# Lora_GPS_Shield_v1_1.net
KiCad netlist of a schematic drawn in EAGLE
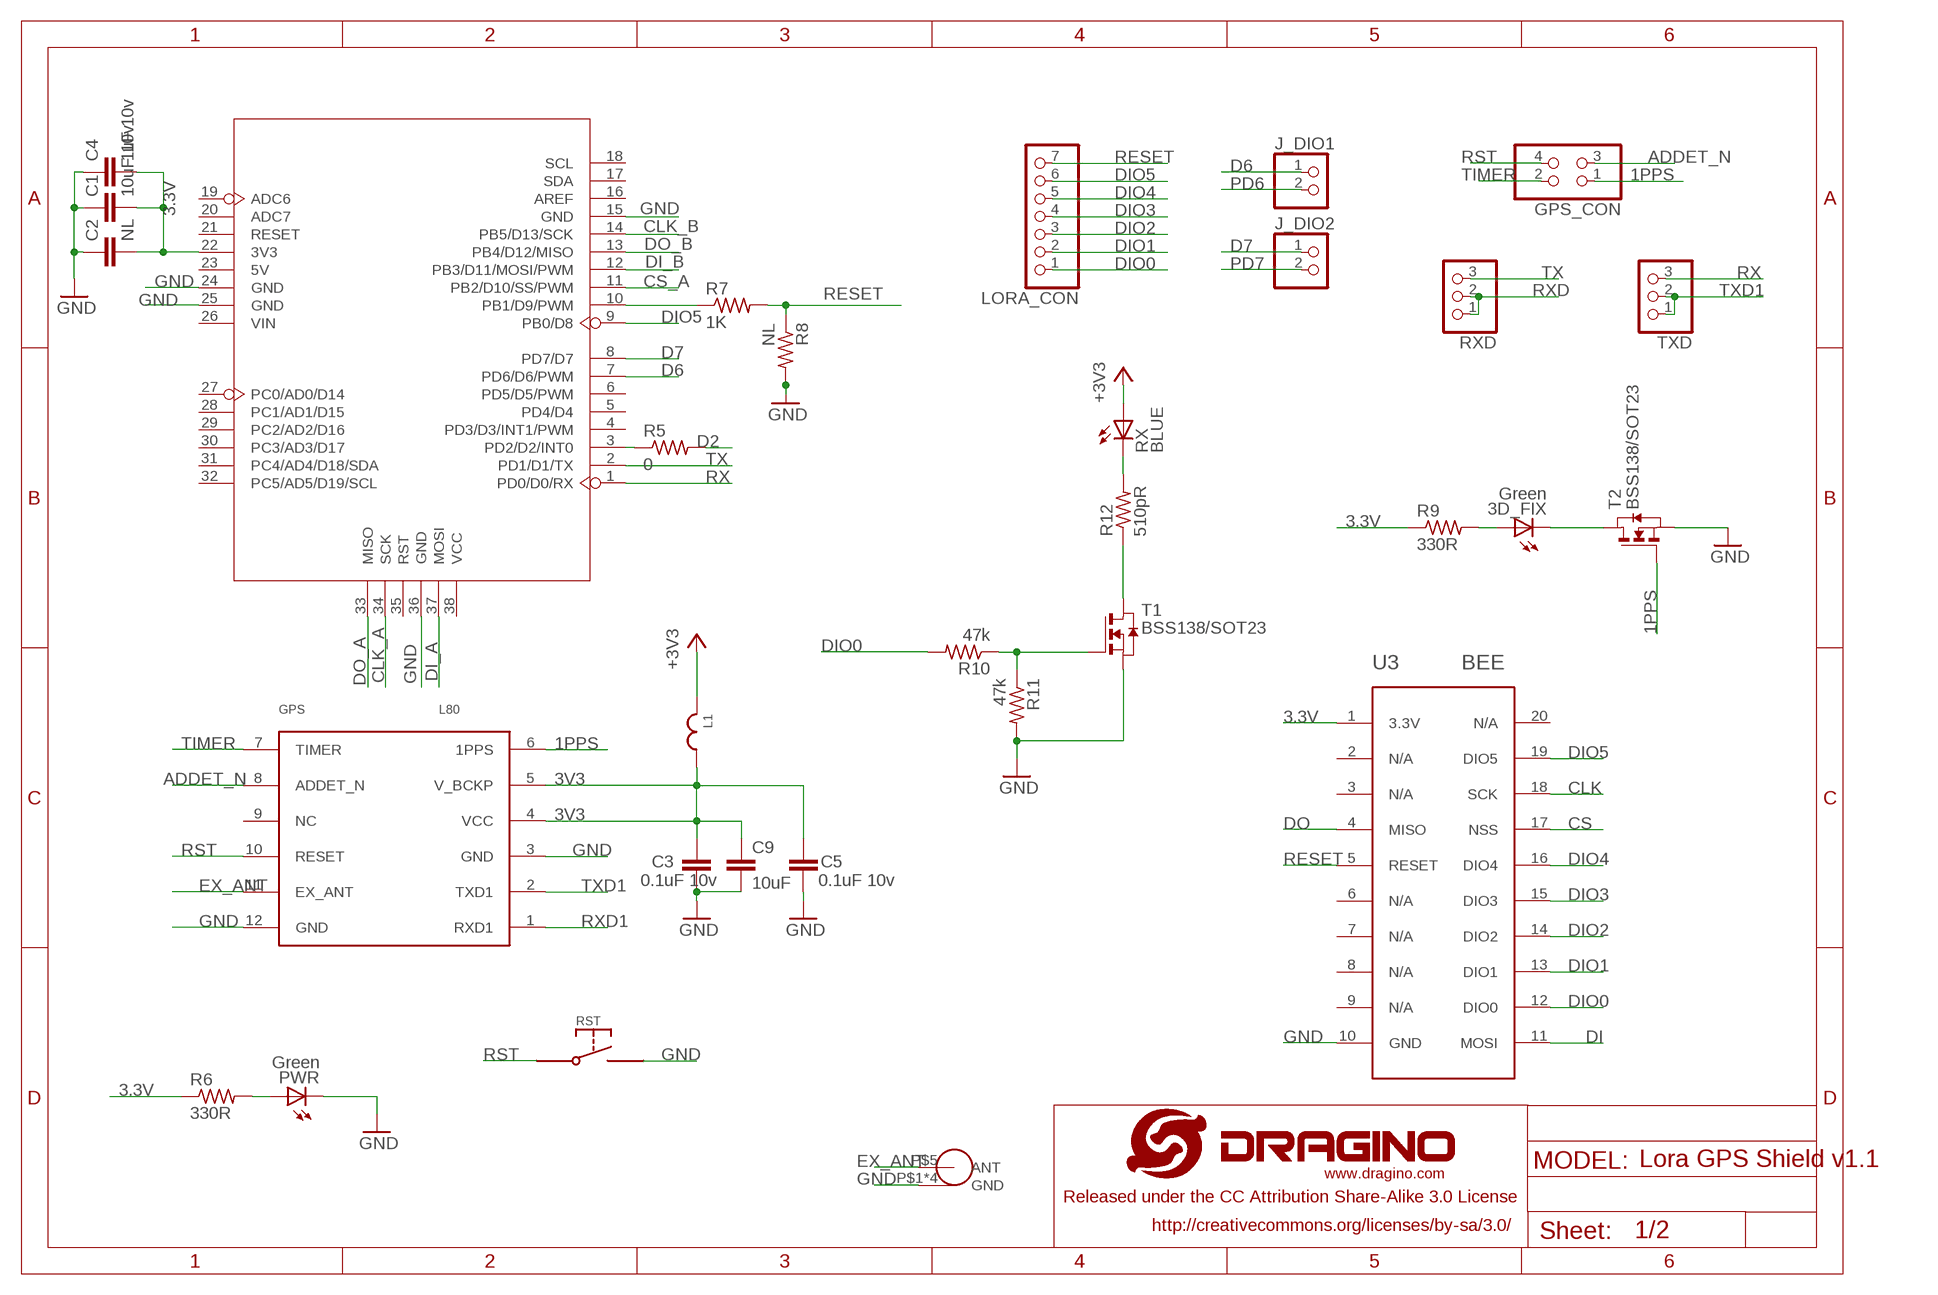
[diagram p0: schematic, sheet 1]
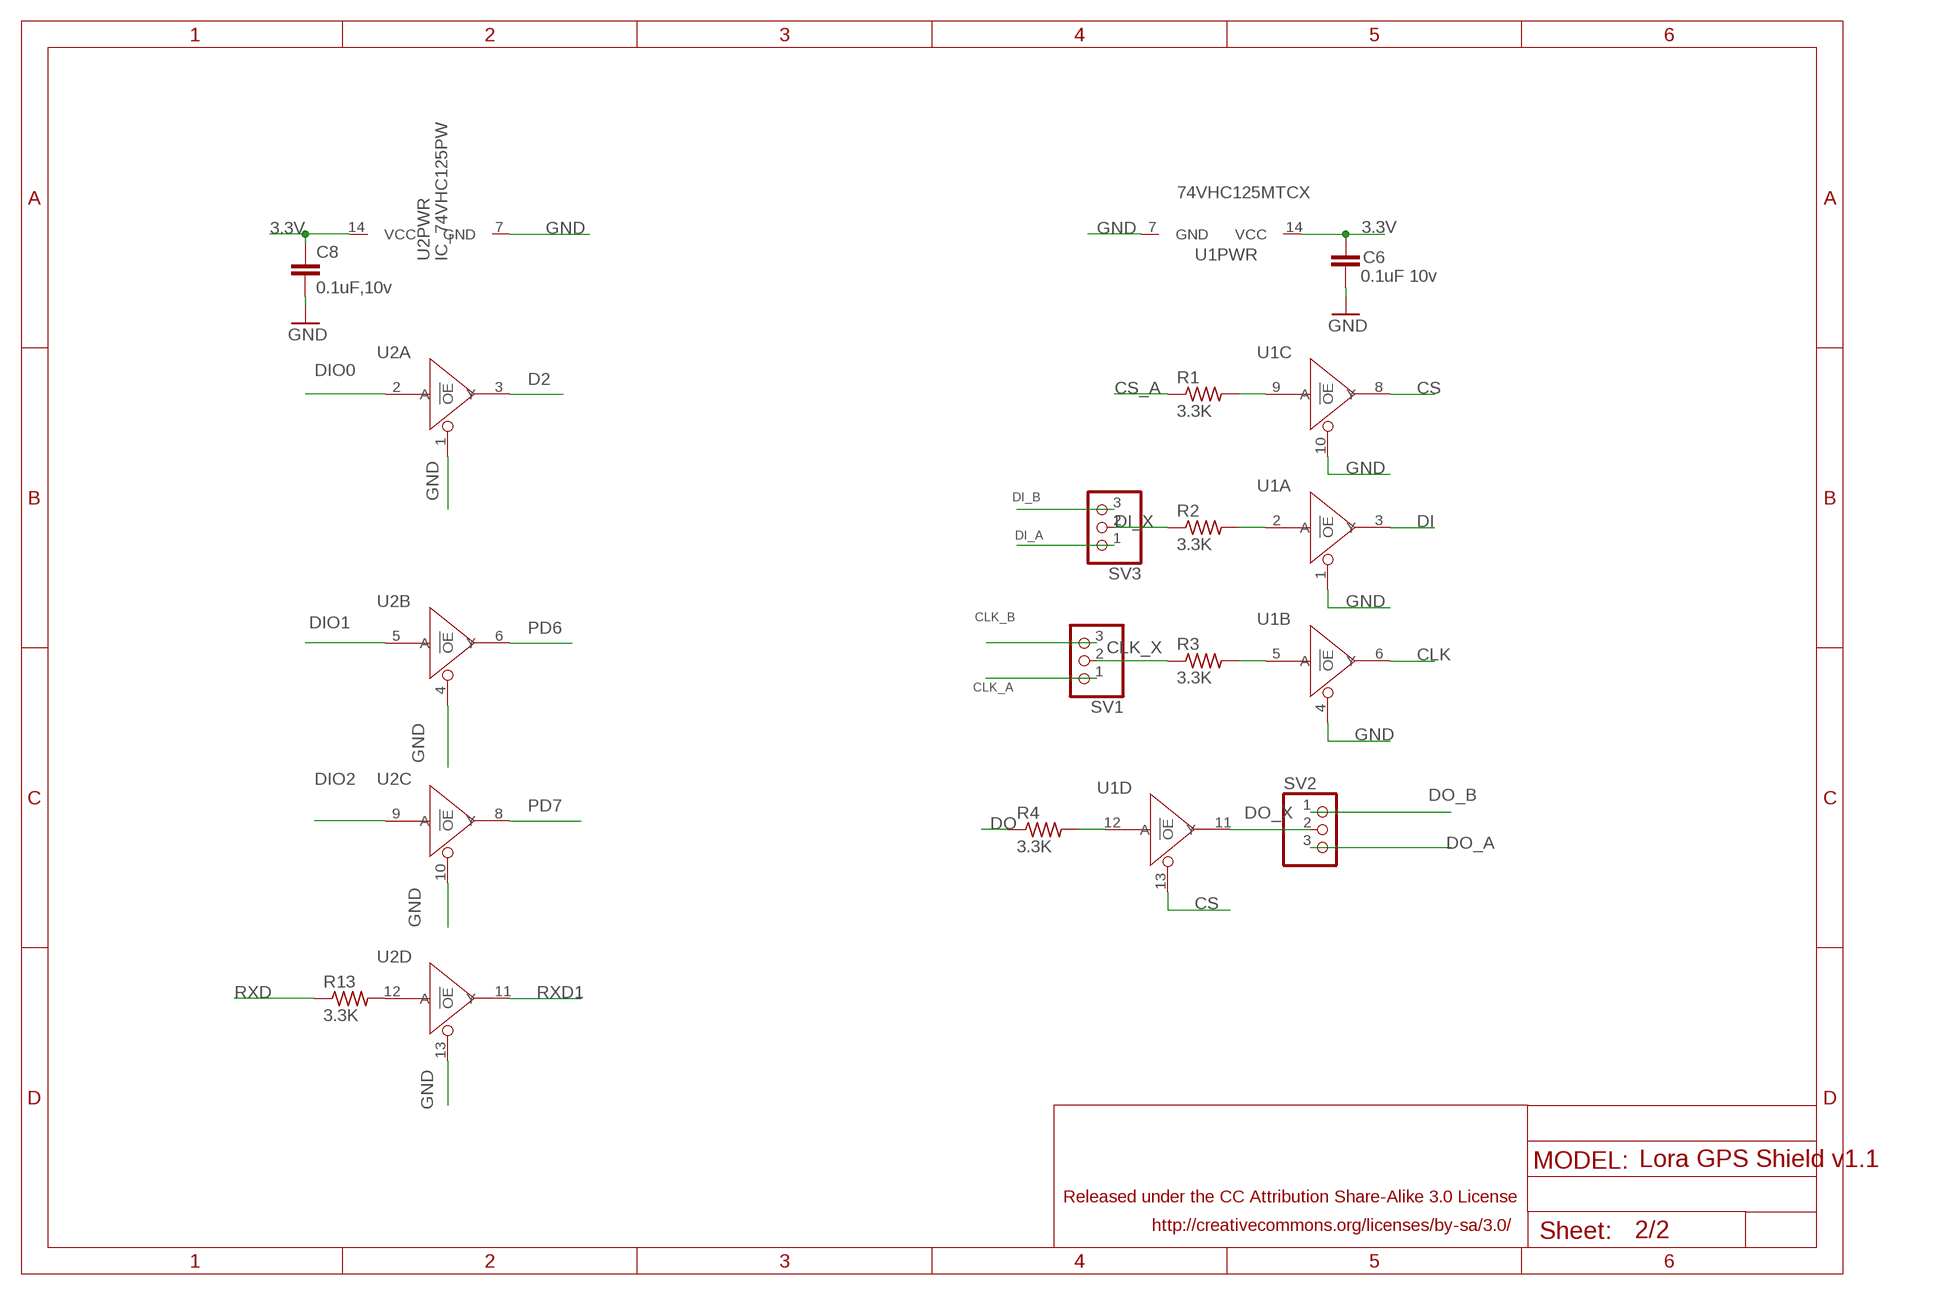
[diagram p1: schematic, sheet 2]

(export (version "E")
  (design (tool "Eeschema 10.0.6"))
  (components
    (comp (ref "3D_FIX")
      (value "Green")
      (footprint "eagle-import:CHIPLED_0603")
      (libsource (lib "eagle-import") (part "LEDCHIPLED_0603"))
    )
    (comp (ref "C1")
      (value "10uF 10v")
      (footprint "eagle-import:C0805")
      (libsource (lib "eagle-import") (part "C-EUC0805"))
    )
    (comp (ref "C2")
      (value "NL")
      (footprint "eagle-import:C0402")
      (libsource (lib "eagle-import") (part "C-EUC0402"))
    )
    (comp (ref "C3")
      (value "0.1uF 10v")
      (footprint "eagle-import:C0402")
      (libsource (lib "eagle-import") (part "C-EUC0402"))
    )
    (comp (ref "C4")
      (value "1uF 10v")
      (footprint "eagle-import:C0402")
      (libsource (lib "eagle-import") (part "C-EUC0402"))
    )
    (comp (ref "C5")
      (value "0.1uF 10v")
      (footprint "eagle-import:C0402")
      (libsource (lib "eagle-import") (part "C-EUC0402"))
    )
    (comp (ref "C9")
      (value "10uF")
      (footprint "eagle-import:C0805")
      (libsource (lib "eagle-import") (part "C-EUC0805"))
    )
    (comp (ref "GPS")
      (value "L80")
      (footprint "eagle-import:L80")
      (libsource (lib "eagle-import") (part "L80"))
    )
    (comp (ref "GPS_ANT")
      (value "NL")
      (footprint "eagle-import:SMA-KE")
      (libsource (lib "eagle-import") (part "SMA-KE"))
    )
    (comp (ref "GPS_CON")
      (value "PINHD-2X2")
      (footprint "eagle-import:2X02")
      (libsource (lib "eagle-import") (part "PINHD-2X2"))
    )
    (comp (ref "J_DIO1")
      (value "PINHD-1X21X2_S")
      (footprint "eagle-import:1X02")
      (libsource (lib "eagle-import") (part "PINHD-1X21X2_S"))
    )
    (comp (ref "J_DIO2")
      (value "PINHD-1X2")
      (footprint "eagle-import:1X02")
      (libsource (lib "eagle-import") (part "PINHD-1X2"))
    )
    (comp (ref "L1")
      (value "JLC-PZ2012D800-3R0TF")
      (footprint "eagle-import:C0805")
      (libsource (lib "eagle-import") (part "BEADS0805"))
    )
    (comp (ref "LORA_CON")
      (value "PINHD-1X71X7_S")
      (footprint "eagle-import:1X07")
      (libsource (lib "eagle-import") (part "PINHD-1X71X7_S"))
    )
    (comp (ref "PWR")
      (value "Green")
      (footprint "eagle-import:DRAGINO_CHIPLED_0603")
      (libsource (lib "eagle-import") (part "DRAGINO_LEDCHIPLED_0603"))
    )
    (comp (ref "R5")
      (value "0")
      (footprint "eagle-import:R0402")
      (libsource (lib "eagle-import") (part "R-US_R0402"))
    )
    (comp (ref "R6")
      (value "330R")
      (footprint "eagle-import:R0402")
      (libsource (lib "eagle-import") (part "R-US_R0402"))
    )
    (comp (ref "R7")
      (value "1K")
      (footprint "eagle-import:R0402")
      (libsource (lib "eagle-import") (part "R-US_R0402"))
    )
    (comp (ref "R8")
      (value "NL")
      (footprint "eagle-import:R0402")
      (libsource (lib "eagle-import") (part "R-US_R0402"))
    )
    (comp (ref "R9")
      (value "330R")
      (footprint "eagle-import:R0402")
      (libsource (lib "eagle-import") (part "R-US_R0402"))
    )
    (comp (ref "R10")
      (value "47k")
      (footprint "eagle-import:R0402")
      (libsource (lib "eagle-import") (part "R-US_R0402"))
    )
    (comp (ref "R11")
      (value "47k")
      (footprint "eagle-import:R0402")
      (libsource (lib "eagle-import") (part "R-US_R0402"))
    )
    (comp (ref "R12")
      (value "510pR")
      (footprint "eagle-import:R0402")
      (libsource (lib "eagle-import") (part "R-US_R0402"))
    )
    (comp (ref "RST")
      (value "SWITCHTS-017")
      (footprint "eagle-import:TS-017")
      (libsource (lib "eagle-import") (part "SWITCHTS-017"))
    )
    (comp (ref "RX")
      (value "BLUE")
      (footprint "eagle-import:CHIPLED_0603")
      (libsource (lib "eagle-import") (part "dragino-passive_LEDCHIPLED_0603"))
    )
    (comp (ref "RXD")
      (value "PINHD-1X3")
      (footprint "eagle-import:1X03")
      (libsource (lib "eagle-import") (part "PINHD-1X3"))
    )
    (comp (ref "T1")
      (value "BSS138/SOT23")
      (footprint "eagle-import:SOT-23")
      (libsource (lib "eagle-import") (part "NMOSFET-SOT23"))
    )
    (comp (ref "T2")
      (value "BSS138/SOT23")
      (footprint "eagle-import:SOT-23")
      (libsource (lib "eagle-import") (part "NMOSFET-SOT23"))
    )
    (comp (ref "TXD")
      (value "PINHD-1X3")
      (footprint "eagle-import:1X03")
      (libsource (lib "eagle-import") (part "PINHD-1X3"))
    )
    (comp (ref "U$1")
      (value "LOGO-NEW")
      (footprint "eagle-import:LOGO-SILK-NEW")
      (libsource (lib "eagle-import") (part "LOGO-NEW"))
    )
    (comp (ref "U3")
      (value "BEE")
      (footprint "eagle-import:LORA")
      (libsource (lib "eagle-import") (part "LORAHAT_S"))
    )
    (comp (ref "U5")
      (value "MOUDLE_ARDUINO-38PMOUDLE_ARDUINO-38P_L")
      (footprint "eagle-import:MOUDLE_ARDUINO-38P_L")
      (libsource (lib "eagle-import") (part "MOUDLE_ARDUINO-38PMOUDLE_ARDUINO-38P_L"))
    )
    (comp (ref "C6")
      (value "0.1uF 10v")
      (footprint "eagle-import:C0402")
      (libsource (lib "eagle-import") (part "C-EUC0402"))
    )
    (comp (ref "C8")
      (value "0.1uF,10v")
      (footprint "eagle-import:C0402")
      (libsource (lib "eagle-import") (part "C-EUC0402"))
    )
    (comp (ref "R1")
      (value "3.3K")
      (footprint "eagle-import:R0402")
      (libsource (lib "eagle-import") (part "R-US_R0402"))
    )
    (comp (ref "R2")
      (value "3.3K")
      (footprint "eagle-import:R0402")
      (libsource (lib "eagle-import") (part "R-US_R0402"))
    )
    (comp (ref "R3")
      (value "3.3K")
      (footprint "eagle-import:R0402")
      (libsource (lib "eagle-import") (part "R-US_R0402"))
    )
    (comp (ref "R4")
      (value "3.3K")
      (footprint "eagle-import:R0402")
      (libsource (lib "eagle-import") (part "R-US_R0402"))
    )
    (comp (ref "R13")
      (value "3.3K")
      (footprint "eagle-import:R0402")
      (libsource (lib "eagle-import") (part "R-US_R0402"))
    )
    (comp (ref "SV1")
      (value "PINHD-1X31X3_S")
      (footprint "eagle-import:1X03")
      (libsource (lib "eagle-import") (part "PINHD-1X31X3_S"))
    )
    (comp (ref "SV2")
      (value "PINHD-1X3")
      (footprint "eagle-import:1X03")
      (libsource (lib "eagle-import") (part "PINHD-1X3"))
    )
    (comp (ref "SV3")
      (value "PINHD-1X3")
      (footprint "eagle-import:1X03")
      (libsource (lib "eagle-import") (part "PINHD-1X3"))
    )
    (comp (ref "U1")
      (value "74VHC125MTCX")
      (footprint "eagle-import:TSSOP14")
      (libsource (lib "eagle-import") (part "IC_74V125PWHC"))
    )
    (comp (ref "U2")
      (value "IC_74VHC125PW")
      (footprint "eagle-import:IC_TSSOP14")
      (libsource (lib "eagle-import") (part "IC_74V125PWHC"))
    )
  )
  (nets
    (net (code "1") (name "1PPS") (class "Default")
      (node (ref "GPS") (pin "6") (pinfunction "1PPS_6") (pintype "bidirectional"))
      (node (ref "GPS_CON") (pin "1") (pinfunction "1_1") (pintype "passive"))
      (node (ref "T2") (pin "3") (pinfunction "G_3") (pintype "passive"))
    )
    (net (code "2") (name "3.3V") (class "Default")
      (node (ref "C1") (pin "2") (pinfunction "2_2") (pintype "passive"))
      (node (ref "C2") (pin "2") (pinfunction "2_2") (pintype "passive"))
      (node (ref "C4") (pin "2") (pinfunction "2_2") (pintype "passive"))
      (node (ref "C6") (pin "2") (pinfunction "2_2") (pintype "passive"))
      (node (ref "C8") (pin "1") (pinfunction "1_1") (pintype "passive"))
      (node (ref "L1") (pin "1") (pinfunction "P$1_1") (pintype "bidirectional"))
      (node (ref "R6") (pin "1") (pinfunction "1_1") (pintype "passive"))
      (node (ref "R9") (pin "1") (pinfunction "1_1") (pintype "passive"))
      (node (ref "RX") (pin "A") (pinfunction "A_A") (pintype "passive"))
      (node (ref "U1") (pin "14") (pinfunction "VCC_14") (pintype "power_in"))
      (node (ref "U2") (pin "14") (pinfunction "VCC_14") (pintype "power_in"))
      (node (ref "U3") (pin "1") (pinfunction "3.3V_1") (pintype "bidirectional"))
      (node (ref "U5") (pin "22") (pinfunction "3V3_22") (pintype "bidirectional"))
    )
    (net (code "3") (name "3V3") (class "Default")
      (node (ref "C3") (pin "2") (pinfunction "2_2") (pintype "passive"))
      (node (ref "C5") (pin "2") (pinfunction "2_2") (pintype "passive"))
      (node (ref "C9") (pin "1") (pinfunction "1_1") (pintype "passive"))
      (node (ref "GPS") (pin "4") (pinfunction "VCC_4") (pintype "bidirectional"))
      (node (ref "GPS") (pin "5") (pinfunction "V_BCKP_5") (pintype "bidirectional"))
      (node (ref "L1") (pin "2") (pinfunction "P$2_2") (pintype "bidirectional"))
    )
    (net (code "4") (name "ADDET_N") (class "Default")
      (node (ref "GPS") (pin "8") (pinfunction "ADDET_N_8") (pintype "bidirectional"))
      (node (ref "GPS_CON") (pin "3") (pinfunction "3_3") (pintype "passive"))
    )
    (net (code "5") (name "CLK") (class "Default")
      (node (ref "U1") (pin "6") (pinfunction "Y_6") (pintype "bidirectional"))
      (node (ref "U3") (pin "18") (pinfunction "SCK_18") (pintype "bidirectional"))
    )
    (net (code "6") (name "CLK_A") (class "Default")
      (node (ref "SV1") (pin "1") (pinfunction "1_1") (pintype "passive"))
      (node (ref "U5") (pin "34") (pinfunction "SCK_34") (pintype "bidirectional"))
    )
    (net (code "7") (name "CLK_B") (class "Default")
      (node (ref "SV1") (pin "3") (pinfunction "3_3") (pintype "passive"))
      (node (ref "U5") (pin "14") (pinfunction "PB5/D13/SCK_14") (pintype "bidirectional"))
    )
    (net (code "8") (name "CLK_X") (class "Default")
      (node (ref "R3") (pin "1") (pinfunction "1_1") (pintype "passive"))
      (node (ref "SV1") (pin "2") (pinfunction "2_2") (pintype "passive"))
    )
    (net (code "9") (name "CS") (class "Default")
      (node (ref "U1") (pin "13") (pinfunction "~{OE}_13") (pintype "bidirectional"))
      (node (ref "U1") (pin "8") (pinfunction "Y_8") (pintype "bidirectional"))
      (node (ref "U3") (pin "17") (pinfunction "NSS_17") (pintype "bidirectional"))
    )
    (net (code "10") (name "CS_A") (class "Default")
      (node (ref "R1") (pin "1") (pinfunction "1_1") (pintype "passive"))
      (node (ref "U5") (pin "11") (pinfunction "PB2/D10/SS/PWM_11") (pintype "bidirectional"))
    )
    (net (code "11") (name "D2") (class "Default")
      (node (ref "R5") (pin "2") (pinfunction "2_2") (pintype "passive"))
      (node (ref "U2") (pin "3") (pinfunction "Y_3") (pintype "bidirectional"))
    )
    (net (code "12") (name "D6") (class "Default")
      (node (ref "J_DIO1") (pin "1") (pinfunction "1_1") (pintype "passive"))
      (node (ref "U5") (pin "7") (pinfunction "PD6/D6/PWM_7") (pintype "bidirectional"))
    )
    (net (code "13") (name "D7") (class "Default")
      (node (ref "J_DIO2") (pin "1") (pinfunction "1_1") (pintype "passive"))
      (node (ref "U5") (pin "8") (pinfunction "PD7/D7_8") (pintype "bidirectional"))
    )
    (net (code "14") (name "DI") (class "Default")
      (node (ref "U1") (pin "3") (pinfunction "Y_3") (pintype "bidirectional"))
      (node (ref "U3") (pin "11") (pinfunction "MOSI_11") (pintype "bidirectional"))
    )
    (net (code "15") (name "DIO0") (class "Default")
      (node (ref "LORA_CON") (pin "1") (pinfunction "1_1") (pintype "passive"))
      (node (ref "R10") (pin "2") (pinfunction "2_2") (pintype "passive"))
      (node (ref "U2") (pin "2") (pinfunction "A_2") (pintype "bidirectional"))
      (node (ref "U3") (pin "12") (pinfunction "DIO0_12") (pintype "bidirectional"))
    )
    (net (code "16") (name "DIO1") (class "Default")
      (node (ref "LORA_CON") (pin "2") (pinfunction "2_2") (pintype "passive"))
      (node (ref "U2") (pin "5") (pinfunction "A_5") (pintype "bidirectional"))
      (node (ref "U3") (pin "13") (pinfunction "DIO1_13") (pintype "bidirectional"))
    )
    (net (code "17") (name "DIO2") (class "Default")
      (node (ref "LORA_CON") (pin "3") (pinfunction "3_3") (pintype "passive"))
      (node (ref "U2") (pin "9") (pinfunction "A_9") (pintype "bidirectional"))
      (node (ref "U3") (pin "14") (pinfunction "DIO2_14") (pintype "bidirectional"))
    )
    (net (code "18") (name "DIO3") (class "Default")
      (node (ref "LORA_CON") (pin "4") (pinfunction "4_4") (pintype "passive"))
      (node (ref "U3") (pin "15") (pinfunction "DIO3_15") (pintype "bidirectional"))
    )
    (net (code "19") (name "DIO4") (class "Default")
      (node (ref "LORA_CON") (pin "5") (pinfunction "5_5") (pintype "passive"))
      (node (ref "U3") (pin "16") (pinfunction "DIO4_16") (pintype "bidirectional"))
    )
    (net (code "20") (name "DIO5") (class "Default")
      (node (ref "LORA_CON") (pin "6") (pinfunction "6_6") (pintype "passive"))
      (node (ref "U3") (pin "19") (pinfunction "DIO5_19") (pintype "bidirectional"))
      (node (ref "U5") (pin "9") (pinfunction "PB0/D8_9") (pintype "bidirectional"))
    )
    (net (code "21") (name "DI_A") (class "Default")
      (node (ref "SV3") (pin "1") (pinfunction "1_1") (pintype "passive"))
      (node (ref "U5") (pin "37") (pinfunction "MOSI_37") (pintype "bidirectional"))
    )
    (net (code "22") (name "DI_B") (class "Default")
      (node (ref "SV3") (pin "3") (pinfunction "3_3") (pintype "passive"))
      (node (ref "U5") (pin "12") (pinfunction "PB3/D11/MOSI/PWM_12") (pintype "bidirectional"))
    )
    (net (code "23") (name "DI_X") (class "Default")
      (node (ref "R2") (pin "1") (pinfunction "1_1") (pintype "passive"))
      (node (ref "SV3") (pin "2") (pinfunction "2_2") (pintype "passive"))
    )
    (net (code "24") (name "DO") (class "Default")
      (node (ref "R4") (pin "1") (pinfunction "1_1") (pintype "passive"))
      (node (ref "U3") (pin "4") (pinfunction "MISO_4") (pintype "bidirectional"))
    )
    (net (code "25") (name "DO_A") (class "Default")
      (node (ref "SV2") (pin "3") (pinfunction "3_3") (pintype "passive"))
      (node (ref "U5") (pin "33") (pinfunction "MISO_33") (pintype "bidirectional"))
    )
    (net (code "26") (name "DO_B") (class "Default")
      (node (ref "SV2") (pin "1") (pinfunction "1_1") (pintype "passive"))
      (node (ref "U5") (pin "13") (pinfunction "PB4/D12/MISO_13") (pintype "bidirectional"))
    )
    (net (code "27") (name "DO_X") (class "Default")
      (node (ref "SV2") (pin "2") (pinfunction "2_2") (pintype "passive"))
      (node (ref "U1") (pin "11") (pinfunction "Y_11") (pintype "bidirectional"))
    )
    (net (code "28") (name "EX_ANT") (class "Default")
      (node (ref "GPS") (pin "11") (pinfunction "EX_ANT_11") (pintype "bidirectional"))
      (node (ref "GPS_ANT") (pin "P$5") (pinfunction "ANT_P$5") (pintype "bidirectional"))
    )
    (net (code "29") (name "GND") (class "Default")
      (node (ref "C1") (pin "1") (pinfunction "1_1") (pintype "passive"))
      (node (ref "C2") (pin "1") (pinfunction "1_1") (pintype "passive"))
      (node (ref "C3") (pin "1") (pinfunction "1_1") (pintype "passive"))
      (node (ref "C4") (pin "1") (pinfunction "1_1") (pintype "passive"))
      (node (ref "C5") (pin "1") (pinfunction "1_1") (pintype "passive"))
      (node (ref "C6") (pin "1") (pinfunction "1_1") (pintype "passive"))
      (node (ref "C8") (pin "2") (pinfunction "2_2") (pintype "passive"))
      (node (ref "C9") (pin "2") (pinfunction "2_2") (pintype "passive"))
      (node (ref "GPS") (pin "12") (pinfunction "GND_12") (pintype "bidirectional"))
      (node (ref "GPS") (pin "3") (pinfunction "GND_3") (pintype "bidirectional"))
      (node (ref "GPS_ANT") (pin "P$1") (pinfunction "GND_P$1") (pintype "bidirectional"))
      (node (ref "GPS_ANT") (pin "P$2") (pinfunction "GND_P$2") (pintype "bidirectional"))
      (node (ref "GPS_ANT") (pin "P$3") (pinfunction "GND_P$3") (pintype "bidirectional"))
      (node (ref "GPS_ANT") (pin "P$4") (pinfunction "GND_P$4") (pintype "bidirectional"))
      (node (ref "PWR") (pin "C") (pinfunction "C_C") (pintype "passive"))
      (node (ref "R11") (pin "2") (pinfunction "2_2") (pintype "passive"))
      (node (ref "R8") (pin "2") (pinfunction "2_2") (pintype "passive"))
      (node (ref "RST") (pin "P$2") (pinfunction "P$2_P$2") (pintype "bidirectional"))
      (node (ref "T1") (pin "2") (pinfunction "S_2") (pintype "passive"))
      (node (ref "T2") (pin "2") (pinfunction "S_2") (pintype "passive"))
      (node (ref "U1") (pin "1") (pinfunction "~{OE}_1") (pintype "bidirectional"))
      (node (ref "U1") (pin "10") (pinfunction "~{OE}_10") (pintype "bidirectional"))
      (node (ref "U1") (pin "4") (pinfunction "~{OE}_4") (pintype "bidirectional"))
      (node (ref "U1") (pin "7") (pinfunction "GND_7") (pintype "power_in"))
      (node (ref "U2") (pin "1") (pinfunction "~{OE}_1") (pintype "bidirectional"))
      (node (ref "U2") (pin "10") (pinfunction "~{OE}_10") (pintype "bidirectional"))
      (node (ref "U2") (pin "13") (pinfunction "~{OE}_13") (pintype "bidirectional"))
      (node (ref "U2") (pin "4") (pinfunction "~{OE}_4") (pintype "bidirectional"))
      (node (ref "U2") (pin "7") (pinfunction "GND_7") (pintype "power_in"))
      (node (ref "U3") (pin "10") (pinfunction "GND_10") (pintype "bidirectional"))
      (node (ref "U5") (pin "15") (pinfunction "GND_15") (pintype "bidirectional"))
      (node (ref "U5") (pin "24") (pinfunction "GND_24") (pintype "bidirectional"))
      (node (ref "U5") (pin "25") (pinfunction "GND_25") (pintype "bidirectional"))
      (node (ref "U5") (pin "36") (pinfunction "GND_36") (pintype "bidirectional"))
    )
    (net (code "30") (name "Net-(3D_FIX-PadA)") (class "Default")
      (node (ref "3D_FIX") (pin "A") (pinfunction "A_A") (pintype "passive"))
      (node (ref "R9") (pin "2") (pinfunction "2_2") (pintype "passive"))
    )
    (net (code "31") (name "Net-(PWR-PadA)") (class "Default")
      (node (ref "PWR") (pin "A") (pinfunction "A_A") (pintype "passive"))
      (node (ref "R6") (pin "2") (pinfunction "2_2") (pintype "passive"))
    )
    (net (code "32") (name "Net-(R12-Pad2)") (class "Default")
      (node (ref "R12") (pin "2") (pinfunction "2_2") (pintype "passive"))
      (node (ref "RX") (pin "C") (pinfunction "C_C") (pintype "passive"))
    )
    (net (code "33") (name "Net-(T1-D)") (class "Default")
      (node (ref "R12") (pin "1") (pinfunction "1_1") (pintype "passive"))
      (node (ref "T1") (pin "1") (pinfunction "D_1") (pintype "passive"))
    )
    (net (code "34") (name "Net-(T1-G)") (class "Default")
      (node (ref "R10") (pin "1") (pinfunction "1_1") (pintype "passive"))
      (node (ref "R11") (pin "1") (pinfunction "1_1") (pintype "passive"))
      (node (ref "T1") (pin "3") (pinfunction "G_3") (pintype "passive"))
    )
    (net (code "35") (name "Net-(T2-D)") (class "Default")
      (node (ref "3D_FIX") (pin "C") (pinfunction "C_C") (pintype "passive"))
      (node (ref "T2") (pin "1") (pinfunction "D_1") (pintype "passive"))
    )
    (net (code "36") (name "Net-(U1A-A)") (class "Default")
      (node (ref "R2") (pin "2") (pinfunction "2_2") (pintype "passive"))
      (node (ref "U1") (pin "2") (pinfunction "A_2") (pintype "bidirectional"))
    )
    (net (code "37") (name "Net-(U1B-A)") (class "Default")
      (node (ref "R3") (pin "2") (pinfunction "2_2") (pintype "passive"))
      (node (ref "U1") (pin "5") (pinfunction "A_5") (pintype "bidirectional"))
    )
    (net (code "38") (name "Net-(U1C-A)") (class "Default")
      (node (ref "R1") (pin "2") (pinfunction "2_2") (pintype "passive"))
      (node (ref "U1") (pin "9") (pinfunction "A_9") (pintype "bidirectional"))
    )
    (net (code "39") (name "Net-(U1D-A)") (class "Default")
      (node (ref "R4") (pin "2") (pinfunction "2_2") (pintype "passive"))
      (node (ref "U1") (pin "12") (pinfunction "A_12") (pintype "bidirectional"))
    )
    (net (code "40") (name "Net-(U2D-A)") (class "Default")
      (node (ref "R13") (pin "2") (pinfunction "2_2") (pintype "passive"))
      (node (ref "U2") (pin "12") (pinfunction "A_12") (pintype "bidirectional"))
    )
    (net (code "41") (name "Net-(U5-PB1{slash}D9{slash}PWM)") (class "Default")
      (node (ref "R7") (pin "1") (pinfunction "1_1") (pintype "passive"))
      (node (ref "U5") (pin "10") (pinfunction "PB1/D9/PWM_10") (pintype "bidirectional"))
    )
    (net (code "42") (name "Net-(U5-PD2{slash}D2{slash}INT0)") (class "Default")
      (node (ref "R5") (pin "1") (pinfunction "1_1") (pintype "passive"))
      (node (ref "U5") (pin "3") (pinfunction "PD2/D2/INT0_3") (pintype "bidirectional"))
    )
    (net (code "43") (name "PD6") (class "Default")
      (node (ref "J_DIO1") (pin "2") (pinfunction "2_2") (pintype "passive"))
      (node (ref "U2") (pin "6") (pinfunction "Y_6") (pintype "bidirectional"))
    )
    (net (code "44") (name "PD7") (class "Default")
      (node (ref "J_DIO2") (pin "2") (pinfunction "2_2") (pintype "passive"))
      (node (ref "U2") (pin "8") (pinfunction "Y_8") (pintype "bidirectional"))
    )
    (net (code "45") (name "RESET") (class "Default")
      (node (ref "LORA_CON") (pin "7") (pinfunction "7_7") (pintype "passive"))
      (node (ref "R7") (pin "2") (pinfunction "2_2") (pintype "passive"))
      (node (ref "R8") (pin "1") (pinfunction "1_1") (pintype "passive"))
      (node (ref "U3") (pin "5") (pinfunction "RESET_5") (pintype "bidirectional"))
    )
    (net (code "46") (name "RST") (class "Default")
      (node (ref "GPS") (pin "10") (pinfunction "RESET_10") (pintype "bidirectional"))
      (node (ref "GPS_CON") (pin "4") (pinfunction "4_4") (pintype "passive"))
      (node (ref "RST") (pin "P$1") (pinfunction "P$1_P$1") (pintype "bidirectional"))
    )
    (net (code "47") (name "RX") (class "Default")
      (node (ref "TXD") (pin "3") (pinfunction "3_3") (pintype "passive"))
      (node (ref "U5") (pin "1") (pinfunction "PD0/D0/RX_1") (pintype "bidirectional"))
    )
    (net (code "48") (name "RXD") (class "Default")
      (node (ref "R13") (pin "1") (pinfunction "1_1") (pintype "passive"))
      (node (ref "RXD") (pin "1") (pinfunction "1_1") (pintype "passive"))
      (node (ref "RXD") (pin "2") (pinfunction "2_2") (pintype "passive"))
    )
    (net (code "49") (name "RXD1") (class "Default")
      (node (ref "GPS") (pin "1") (pinfunction "RXD1_1") (pintype "bidirectional"))
      (node (ref "U2") (pin "11") (pinfunction "Y_11") (pintype "bidirectional"))
    )
    (net (code "50") (name "TIMER") (class "Default")
      (node (ref "GPS") (pin "7") (pinfunction "TIMER_7") (pintype "bidirectional"))
      (node (ref "GPS_CON") (pin "2") (pinfunction "2_2") (pintype "passive"))
    )
    (net (code "51") (name "TX") (class "Default")
      (node (ref "RXD") (pin "3") (pinfunction "3_3") (pintype "passive"))
      (node (ref "U5") (pin "2") (pinfunction "PD1/D1/TX_2") (pintype "bidirectional"))
    )
    (net (code "52") (name "TXD1") (class "Default")
      (node (ref "GPS") (pin "2") (pinfunction "TXD1_2") (pintype "bidirectional"))
      (node (ref "TXD") (pin "1") (pinfunction "1_1") (pintype "passive"))
      (node (ref "TXD") (pin "2") (pinfunction "2_2") (pintype "passive"))
    )
    (net (code "53") (name "unconnected-(GPS-NC-Pad9)") (class "Default")
      (node (ref "GPS") (pin "9") (pinfunction "NC_9") (pintype "bidirectional"))
    )
    (net (code "54") (name "unconnected-(U3-N{slash}A-Pad2)") (class "Default")
      (node (ref "U3") (pin "2") (pinfunction "N/A_2") (pintype "bidirectional"))
    )
    (net (code "55") (name "unconnected-(U3-N{slash}A-Pad3)") (class "Default")
      (node (ref "U3") (pin "3") (pinfunction "N/A_3") (pintype "bidirectional"))
    )
    (net (code "56") (name "unconnected-(U3-N{slash}A-Pad6)") (class "Default")
      (node (ref "U3") (pin "6") (pinfunction "N/A_6") (pintype "bidirectional"))
    )
    (net (code "57") (name "unconnected-(U3-N{slash}A-Pad7)") (class "Default")
      (node (ref "U3") (pin "7") (pinfunction "N/A_7") (pintype "bidirectional"))
    )
    (net (code "58") (name "unconnected-(U3-N{slash}A-Pad8)") (class "Default")
      (node (ref "U3") (pin "8") (pinfunction "N/A_8") (pintype "bidirectional"))
    )
    (net (code "59") (name "unconnected-(U3-N{slash}A-Pad9)") (class "Default")
      (node (ref "U3") (pin "9") (pinfunction "N/A_9") (pintype "bidirectional"))
    )
    (net (code "60") (name "unconnected-(U3-N{slash}A-Pad20)") (class "Default")
      (node (ref "U3") (pin "20") (pinfunction "N/A_20") (pintype "bidirectional"))
    )
    (net (code "61") (name "unconnected-(U5-5V-Pad23)") (class "Default")
      (node (ref "U5") (pin "23") (pinfunction "5V_23") (pintype "bidirectional"))
    )
    (net (code "62") (name "unconnected-(U5-ADC6-Pad19)") (class "Default")
      (node (ref "U5") (pin "19") (pinfunction "ADC6_19") (pintype "bidirectional"))
    )
    (net (code "63") (name "unconnected-(U5-ADC7-Pad20)") (class "Default")
      (node (ref "U5") (pin "20") (pinfunction "ADC7_20") (pintype "bidirectional"))
    )
    (net (code "64") (name "unconnected-(U5-AREF-Pad16)") (class "Default")
      (node (ref "U5") (pin "16") (pinfunction "AREF_16") (pintype "bidirectional"))
    )
    (net (code "65") (name "unconnected-(U5-PC0{slash}AD0{slash}D14-Pad27)") (class "Default")
      (node (ref "U5") (pin "27") (pinfunction "PC0/AD0/D14_27") (pintype "bidirectional"))
    )
    (net (code "66") (name "unconnected-(U5-PC1{slash}AD1{slash}D15-Pad28)") (class "Default")
      (node (ref "U5") (pin "28") (pinfunction "PC1/AD1/D15_28") (pintype "bidirectional"))
    )
    (net (code "67") (name "unconnected-(U5-PC2{slash}AD2{slash}D16-Pad29)") (class "Default")
      (node (ref "U5") (pin "29") (pinfunction "PC2/AD2/D16_29") (pintype "bidirectional"))
    )
    (net (code "68") (name "unconnected-(U5-PC3{slash}AD3{slash}D17-Pad30)") (class "Default")
      (node (ref "U5") (pin "30") (pinfunction "PC3/AD3/D17_30") (pintype "bidirectional"))
    )
    (net (code "69") (name "unconnected-(U5-PC4{slash}AD4{slash}D18{slash}SDA-Pad31)") (class "Default")
      (node (ref "U5") (pin "31") (pinfunction "PC4/AD4/D18/SDA_31") (pintype "bidirectional"))
    )
    (net (code "70") (name "unconnected-(U5-PC5{slash}AD5{slash}D19{slash}SCL-Pad32)") (class "Default")
      (node (ref "U5") (pin "32") (pinfunction "PC5/AD5/D19/SCL_32") (pintype "bidirectional"))
    )
    (net (code "71") (name "unconnected-(U5-PD3{slash}D3{slash}INT1{slash}PWM-Pad4)") (class "Default")
      (node (ref "U5") (pin "4") (pinfunction "PD3/D3/INT1/PWM_4") (pintype "bidirectional"))
    )
    (net (code "72") (name "unconnected-(U5-PD4{slash}D4-Pad5)") (class "Default")
      (node (ref "U5") (pin "5") (pinfunction "PD4/D4_5") (pintype "bidirectional"))
    )
    (net (code "73") (name "unconnected-(U5-PD5{slash}D5{slash}PWM-Pad6)") (class "Default")
      (node (ref "U5") (pin "6") (pinfunction "PD5/D5/PWM_6") (pintype "bidirectional"))
    )
    (net (code "74") (name "unconnected-(U5-RESET-Pad21)") (class "Default")
      (node (ref "U5") (pin "21") (pinfunction "RESET_21") (pintype "bidirectional"))
    )
    (net (code "75") (name "unconnected-(U5-RST-Pad35)") (class "Default")
      (node (ref "U5") (pin "35") (pinfunction "RST_35") (pintype "bidirectional"))
    )
    (net (code "76") (name "unconnected-(U5-SCL-Pad18)") (class "Default")
      (node (ref "U5") (pin "18") (pinfunction "SCL_18") (pintype "bidirectional"))
    )
    (net (code "77") (name "unconnected-(U5-SDA-Pad17)") (class "Default")
      (node (ref "U5") (pin "17") (pinfunction "SDA_17") (pintype "bidirectional"))
    )
    (net (code "78") (name "unconnected-(U5-VCC-Pad38)") (class "Default")
      (node (ref "U5") (pin "38") (pinfunction "VCC_38") (pintype "bidirectional"))
    )
    (net (code "79") (name "unconnected-(U5-VIN-Pad26)") (class "Default")
      (node (ref "U5") (pin "26") (pinfunction "VIN_26") (pintype "bidirectional"))
    )
  )
)
